# Supply.net
KiCad netlist of a schematic drawn in Altium Designer
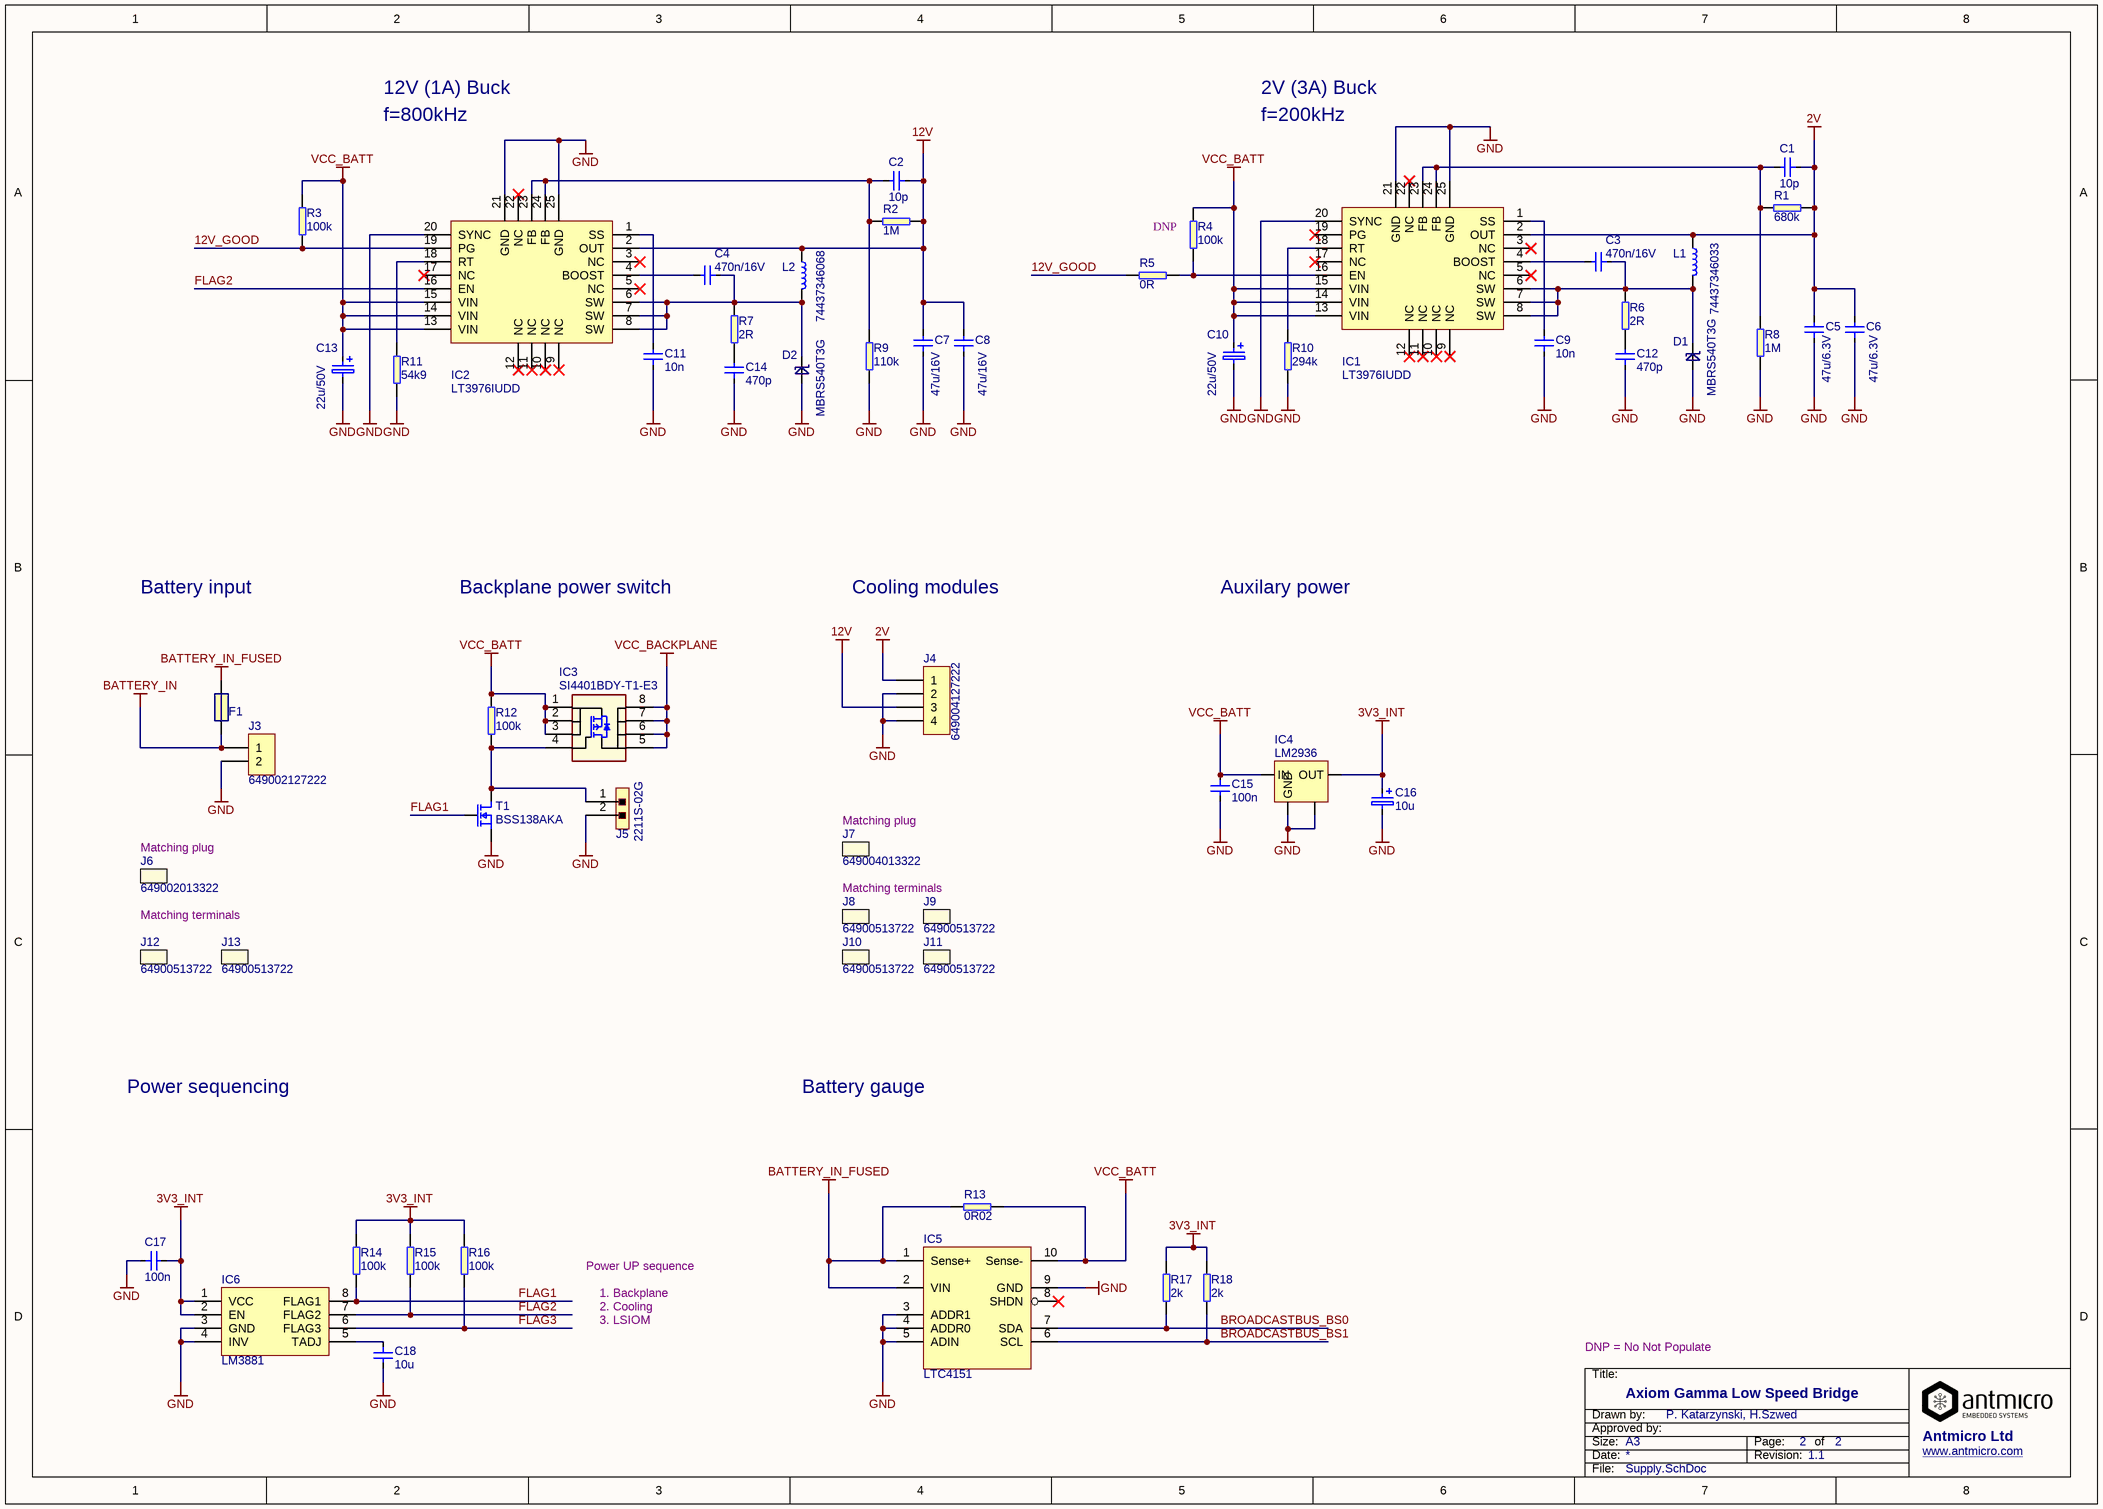
[diagram p0: Supply.SchDoc]

(export (version "E")
  (design (tool "Eeschema 10.0.6"))
  (components
    (comp (ref "C1")
      (value "10p")
      (footprint "0402")
      (description "MLCC SMT Capacitor 0402")
      (fields (field (name "PART NUMBER") "C_10n_0402") (field (name "MANUFACTURER") "AVX"))
      (libsource (lib "Axiom_Gamma_LSB") (part "C_0402"))
    )
    (comp (ref "C2")
      (value "10p")
      (footprint "0402")
      (description "MLCC SMT Capacitor 0402")
      (fields (field (name "PART NUMBER") "C_10n_0402") (field (name "MANUFACTURER") "AVX"))
      (libsource (lib "Axiom_Gamma_LSB") (part "C_0402"))
    )
    (comp (ref "C3")
      (value "470n/16V")
      (footprint "0402")
      (description "MLCC SMT Capacitor 0402")
      (fields (field (name "PART NUMBER") "C_10n_0402") (field (name "MANUFACTURER") "AVX"))
      (libsource (lib "Axiom_Gamma_LSB") (part "C_0402"))
    )
    (comp (ref "C4")
      (value "470n/16V")
      (footprint "0402")
      (description "MLCC SMT Capacitor 0402")
      (fields (field (name "PART NUMBER") "C_10n_0402") (field (name "MANUFACTURER") "AVX"))
      (libsource (lib "Axiom_Gamma_LSB") (part "C_0402"))
    )
    (comp (ref "C5")
      (value "47u/6.3V")
      (footprint "1206")
      (description "MLCC SMT Capacitor 1206")
      (fields (field (name "PART NUMBER") "C_47u_1206") (field (name "MANUFACTURER") "MURATA"))
      (libsource (lib "Axiom_Gamma_LSB") (part "C_1206"))
    )
    (comp (ref "C6")
      (value "47u/6.3V")
      (footprint "1206")
      (description "MLCC SMT Capacitor 1206")
      (fields (field (name "PART NUMBER") "C_47u_1206") (field (name "MANUFACTURER") "MURATA"))
      (libsource (lib "Axiom_Gamma_LSB") (part "C_1206"))
    )
    (comp (ref "C7")
      (value "47u/16V")
      (footprint "1206")
      (description "MLCC SMT Capacitor 1206")
      (fields (field (name "PART NUMBER") "C_47u_1206") (field (name "MANUFACTURER") "MURATA"))
      (libsource (lib "Axiom_Gamma_LSB") (part "C_1206"))
    )
    (comp (ref "C8")
      (value "47u/16V")
      (footprint "1206")
      (description "MLCC SMT Capacitor 1206")
      (fields (field (name "PART NUMBER") "C_47u_1206") (field (name "MANUFACTURER") "MURATA"))
      (libsource (lib "Axiom_Gamma_LSB") (part "C_1206"))
    )
    (comp (ref "C9")
      (value "10n")
      (footprint "0402")
      (description "MLCC SMT Capacitor 0402")
      (fields (field (name "PART NUMBER") "C_10n_0402") (field (name "MANUFACTURER") "AVX"))
      (libsource (lib "Axiom_Gamma_LSB") (part "C_0402"))
    )
    (comp (ref "C10")
      (value "22u/50V")
      (footprint "KEMET_X")
      (description "Tantalum SMT Capacitor Case KEMET_X")
      (fields (field (name "PART NUMBER") "C_22u_KEMET_X") (field (name "MANUFACTURER") "KEMET"))
      (libsource (lib "Axiom_Gamma_LSB") (part "CPol_X"))
    )
    (comp (ref "C11")
      (value "10n")
      (footprint "0402")
      (description "MLCC SMT Capacitor 0402")
      (fields (field (name "PART NUMBER") "C_10n_0402") (field (name "MANUFACTURER") "AVX"))
      (libsource (lib "Axiom_Gamma_LSB") (part "C_0402"))
    )
    (comp (ref "C12")
      (value "470p")
      (footprint "0402")
      (description "MLCC SMT Capacitor 0402")
      (fields (field (name "PART NUMBER") "C_10n_0402") (field (name "MANUFACTURER") "AVX"))
      (libsource (lib "Axiom_Gamma_LSB") (part "C_0402"))
    )
    (comp (ref "C13")
      (value "22u/50V")
      (footprint "KEMET_X")
      (description "Tantalum SMT Capacitor Case KEMET_X")
      (fields (field (name "PART NUMBER") "C_22u_KEMET_X") (field (name "MANUFACTURER") "KEMET"))
      (libsource (lib "Axiom_Gamma_LSB") (part "CPol_X"))
    )
    (comp (ref "C14")
      (value "470p")
      (footprint "0402")
      (description "MLCC SMT Capacitor 0402")
      (fields (field (name "PART NUMBER") "C_10n_0402") (field (name "MANUFACTURER") "AVX"))
      (libsource (lib "Axiom_Gamma_LSB") (part "C_0402"))
    )
    (comp (ref "C15")
      (value "100n")
      (footprint "0603")
      (description "MLCC SMT Capacitor  0603")
      (fields (field (name "PART NUMBER") "C_10u_0603") (field (name "MANUFACTURER") "MULTICOMP"))
      (libsource (lib "Axiom_Gamma_LSB") (part "C_0603"))
    )
    (comp (ref "C16")
      (value "10u")
      (footprint "KEMET_A")
      (description "Tantalum SMT Capacitor Case KEMET_A")
      (fields (field (name "PART NUMBER") "C_10u_KEMET_A") (field (name "MANUFACTURER") "VISHAY"))
      (libsource (lib "Axiom_Gamma_LSB") (part "CPol_A"))
    )
    (comp (ref "C17")
      (value "100n")
      (footprint "0603")
      (description "MLCC SMT Capacitor  0603")
      (fields (field (name "PART NUMBER") "C_10u_0603") (field (name "MANUFACTURER") "MULTICOMP"))
      (libsource (lib "Axiom_Gamma_LSB") (part "C_0603"))
    )
    (comp (ref "C18")
      (value "10u")
      (footprint "0603")
      (description "MLCC SMT Capacitor  0603")
      (fields (field (name "PART NUMBER") "C_10u_0603") (field (name "MANUFACTURER") "MULTICOMP"))
      (libsource (lib "Axiom_Gamma_LSB") (part "C_0603"))
    )
    (comp (ref "D1")
      (value "MBRS540T3G")
      (footprint "SMC-403-03")
      (description "ON SEMICONDUCTOR  MBRS540T3G  Rectifier Diode, Single, 40 V, 5 A, 500 mV, 190 A, 150 °C")
      (fields (field (name "MANUFACTURER") "ON SEMICONDUCTOR"))
      (libsource (lib "Axiom_Gamma_LSB") (part "Diode Schottky"))
    )
    (comp (ref "D2")
      (value "MBRS540T3G")
      (footprint "SMC-403-03")
      (description "ON SEMICONDUCTOR  MBRS540T3G  Rectifier Diode, Single, 40 V, 5 A, 500 mV, 190 A, 150 °C")
      (fields (field (name "MANUFACTURER") "ON SEMICONDUCTOR"))
      (libsource (lib "Axiom_Gamma_LSB") (part "Diode Schottky"))
    )
    (comp (ref "F1")
      (value "MC12CF")
      (footprint "1206")
      (fields (field (name "MANUFACTURER") "MULTICOMP"))
      (libsource (lib "Axiom_Gamma_LSB") (part "Fuse"))
    )
    (comp (ref "IC1")
      (value "LT3976IUDD")
      (footprint "QFN-24_3x5mm")
      (fields (field (name "MANUFACTURER") "LINEAR TECHNOLOGY"))
      (libsource (lib "Axiom_Gamma_LSB") (part "LT3976IUDD"))
    )
    (comp (ref "IC2")
      (value "LT3976IUDD")
      (footprint "QFN-24_3x5mm")
      (fields (field (name "MANUFACTURER") "LINEAR TECHNOLOGY"))
      (libsource (lib "Axiom_Gamma_LSB") (part "LT3976IUDD"))
    )
    (comp (ref "IC3")
      (value "SI4401BDY-T1-E3")
      (footprint "SOIC-SN8_M")
      (description "VISHAY  SI4401BDY-T1-E3  MOSFET Transistor, P Channel, -8.7 A, -40 V, 0.011 ohm, -10 V, -3 V")
      (fields (field (name "MANUFACTURER") "VISHAY"))
      (libsource (lib "Axiom_Gamma_LSB") (part "SI4447DY-T1-E3"))
    )
    (comp (ref "IC4")
      (value "LM2936")
      (footprint "SOT223")
      (fields (field (name "MANUFACTURER") "TEXAS INSTRUMENTS"))
      (libsource (lib "Axiom_Gamma_LSB") (part "LM2936"))
    )
    (comp (ref "IC5")
      (value "LTC4151")
      (footprint "MSOP10")
      (fields (field (name "MANUFACTURER") "LINEAR TECHNOLOGY"))
      (libsource (lib "Axiom_Gamma_LSB") (part "LTC4151"))
    )
    (comp (ref "IC6")
      (value "LM3881")
      (footprint "MSOP-8")
      (description "TEXAS INSTRUMENTS  LM3881MME/NOPB  Power Sequencer, 3-Monitors, 2.7V-5.5Vin,VSSOP-8")
      (fields (field (name "MANUFACTURER") "TEXAS INSTRUMENTS"))
      (libsource (lib "Axiom_Gamma_LSB") (part "LM3881"))
    )
    (comp (ref "J3")
      (value "649002127222")
      (footprint "WE_649002127222")
      (description "4.20mm Male Single Row Angled Header w. Mounting Pegs WR-MPC4")
      (fields (field (name "PART NUMBER") "WE_649002127222") (field (name "MANUFACTURER") "WURTH ELEKTRONIC"))
      (libsource (lib "Axiom_Gamma_LSB") (part "WE_649002127222"))
    )
    (comp (ref "J4")
      (value "649004127222")
      (footprint "WE_649004127222")
      (description "4.20mm Male Single Row Angled Header w. Mounting Pegs WR-MPC4")
      (fields (field (name "PART NUMBER") "WE_649004127222") (field (name "MANUFACTURER") "WURTH ELEKTRONIC"))
      (libsource (lib "Axiom_Gamma_LSB") (part "WE_649004127222"))
    )
    (comp (ref "J5")
      (value "2211S-02G")
      (footprint "HEADER_1X2_male 2.54mm Angle")
      (description "1x2 pinhead male angle")
      (fields
        (field (name "PART NUMBER") "HEADER_1X2_male_angle")
        (field (name "Comment") "1x2 pinhead 2.54mm male")
      )
      (libsource (lib "Axiom_Gamma_LSB") (part "HEADER_1X2_male_angle"))
    )
    (comp (ref "J6")
      (value "649002013322")
      (fields (field (name "MANUFACTURER") "Wuerth Elektronik"))
      (libsource (lib "Axiom_Gamma_LSB") (part "GENERIC_BOM_ONLY"))
    )
    (comp (ref "J7")
      (value "649004013322")
      (fields (field (name "MANUFACTURER") "Wuerth Elektronik"))
      (libsource (lib "Axiom_Gamma_LSB") (part "GENERIC_BOM_ONLY"))
    )
    (comp (ref "J8")
      (value "64900513722")
      (fields (field (name "MANUFACTURER") "Wuerth Elektronik"))
      (libsource (lib "Axiom_Gamma_LSB") (part "GENERIC_BOM_ONLY"))
    )
    (comp (ref "J9")
      (value "64900513722")
      (fields (field (name "MANUFACTURER") "Wuerth Elektronik"))
      (libsource (lib "Axiom_Gamma_LSB") (part "GENERIC_BOM_ONLY"))
    )
    (comp (ref "J10")
      (value "64900513722")
      (fields (field (name "MANUFACTURER") "Wuerth Elektronik"))
      (libsource (lib "Axiom_Gamma_LSB") (part "GENERIC_BOM_ONLY"))
    )
    (comp (ref "J11")
      (value "64900513722")
      (fields (field (name "MANUFACTURER") "Wuerth Elektronik"))
      (libsource (lib "Axiom_Gamma_LSB") (part "GENERIC_BOM_ONLY"))
    )
    (comp (ref "J12")
      (value "64900513722")
      (fields (field (name "MANUFACTURER") "Wuerth Elektronik"))
      (libsource (lib "Axiom_Gamma_LSB") (part "GENERIC_BOM_ONLY"))
    )
    (comp (ref "J13")
      (value "64900513722")
      (fields (field (name "MANUFACTURER") "Wuerth Elektronik"))
      (libsource (lib "Axiom_Gamma_LSB") (part "GENERIC_BOM_ONLY"))
    )
    (comp (ref "L1")
      (value "74437346033")
      (footprint "WE-LHMI")
      (description "3.3 uH, 5.0A, 0.03 ohm, SMD Power Inductor")
      (fields
        (field (name "PART NUMBER") "Wurth-74437346033")
        (field (name "MANUFACTURER") "WURTH ELEKTRONIK")
      )
      (libsource (lib "Axiom_Gamma_LSB") (part "Inductor SMT"))
    )
    (comp (ref "L2")
      (value "74437346068")
      (footprint "WE-LHMI")
      (description "6.8 uH, 3.4A, 0.054 ohm, SMD Power Inductor")
      (fields
        (field (name "PART NUMBER") "Wurth-74437346068")
        (field (name "MANUFACTURER") "WURTH ELEKTRONIK")
      )
      (libsource (lib "Axiom_Gamma_LSB") (part "Inductor SMT"))
    )
    (comp (ref "R1")
      (value "680k")
      (footprint "0402")
      (description "SMT Resistor 0402")
      (fields (field (name "PART NUMBER") "R_2R_0402") (field (name "MANUFACTURER") "MULTICOMP"))
      (libsource (lib "Axiom_Gamma_LSB") (part "R_0402"))
    )
    (comp (ref "R2")
      (value "1M")
      (footprint "0603")
      (description "SMT Resistor 0603")
      (fields (field (name "PART NUMBER") "R_1M_0603_0.1%") (field (name "MANUFACTURER") "TE"))
      (libsource (lib "") (part "R_0603_1"))
    )
    (comp (ref "R3")
      (value "100k")
      (footprint "0603")
      (description "SMT Resistor 0603")
      (fields (field (name "PART NUMBER") "R_1M_0603_0.1%") (field (name "MANUFACTURER") "TE"))
      (libsource (lib "Axiom_Gamma_LSB") (part "R_0603"))
    )
    (comp (ref "R4")
      (value "100k")
      (footprint "0603")
      (description "SMT Resistor 0603")
      (fields (field (name "PART NUMBER") "R_1M_0603_0.1%") (field (name "MANUFACTURER") "TE"))
      (libsource (lib "Axiom_Gamma_LSB") (part "R_0603"))
    )
    (comp (ref "R5")
      (value "0R")
      (footprint "0603")
      (description "SMT Resistor 0603")
      (fields (field (name "PART NUMBER") "R_1M_0603_0.1%") (field (name "MANUFACTURER") "TE"))
      (libsource (lib "") (part "R_0603_2"))
    )
    (comp (ref "R6")
      (value "2R")
      (footprint "0402")
      (description "SMT Resistor 0402")
      (fields (field (name "PART NUMBER") "R_2R_0402") (field (name "MANUFACTURER") "MULTICOMP"))
      (libsource (lib "Axiom_Gamma_LSB") (part "R_0402"))
    )
    (comp (ref "R7")
      (value "2R")
      (footprint "0402")
      (description "SMT Resistor 0402")
      (fields (field (name "PART NUMBER") "R_2R_0402") (field (name "MANUFACTURER") "MULTICOMP"))
      (libsource (lib "Axiom_Gamma_LSB") (part "R_0402"))
    )
    (comp (ref "R8")
      (value "1M")
      (footprint "0603")
      (description "SMT Resistor 0603")
      (fields (field (name "PART NUMBER") "R_1M_0603_0.1%") (field (name "MANUFACTURER") "TE"))
      (libsource (lib "") (part "R_0603_3"))
    )
    (comp (ref "R9")
      (value "110k")
      (footprint "0603")
      (description "SMT Resistor 0603")
      (fields (field (name "PART NUMBER") "R_1M_0603_0.1%") (field (name "MANUFACTURER") "TE"))
      (libsource (lib "") (part "R_0603_2"))
    )
    (comp (ref "R10")
      (value "294k")
      (footprint "0402")
      (description "SMT Resistor 0402")
      (fields (field (name "PART NUMBER") "R_2R_0402") (field (name "MANUFACTURER") "MULTICOMP"))
      (libsource (lib "") (part "R_0402_1"))
    )
    (comp (ref "R11")
      (value "54k9")
      (footprint "0402")
      (description "SMT Resistor 0402")
      (fields (field (name "PART NUMBER") "R_2R_0402") (field (name "MANUFACTURER") "MULTICOMP"))
      (libsource (lib "Axiom_Gamma_LSB") (part "R_0402"))
    )
    (comp (ref "R12")
      (value "100k")
      (footprint "0603")
      (description "SMT Resistor 0603")
      (fields (field (name "PART NUMBER") "R_1M_0603_0.1%") (field (name "MANUFACTURER") "TE"))
      (libsource (lib "Axiom_Gamma_LSB") (part "R_0603"))
    )
    (comp (ref "R13")
      (value "0R02")
      (footprint "2512")
      (description "SMT Resistor 2512")
      (fields (field (name "PART NUMBER") "R_0R02_2512") (field (name "MANUFACTURER") "BOURNS"))
      (libsource (lib "Axiom_Gamma_LSB") (part "R_2512"))
    )
    (comp (ref "R14")
      (value "100k")
      (footprint "0603")
      (description "SMT Resistor 0603")
      (fields (field (name "PART NUMBER") "R_1M_0603_0.1%") (field (name "MANUFACTURER") "TE"))
      (libsource (lib "Axiom_Gamma_LSB") (part "R_0603"))
    )
    (comp (ref "R15")
      (value "100k")
      (footprint "0603")
      (description "SMT Resistor 0603")
      (fields (field (name "PART NUMBER") "R_1M_0603_0.1%") (field (name "MANUFACTURER") "TE"))
      (libsource (lib "Axiom_Gamma_LSB") (part "R_0603"))
    )
    (comp (ref "R16")
      (value "100k")
      (footprint "0603")
      (description "SMT Resistor 0603")
      (fields (field (name "PART NUMBER") "R_1M_0603_0.1%") (field (name "MANUFACTURER") "TE"))
      (libsource (lib "Axiom_Gamma_LSB") (part "R_0603"))
    )
    (comp (ref "R17")
      (value "2k")
      (footprint "0603")
      (description "SMT Resistor 0603")
      (fields (field (name "PART NUMBER") "R_1M_0603_0.1%") (field (name "MANUFACTURER") "TE"))
      (libsource (lib "Axiom_Gamma_LSB") (part "R_0603"))
    )
    (comp (ref "R18")
      (value "2k")
      (footprint "0603")
      (description "SMT Resistor 0603")
      (fields (field (name "PART NUMBER") "R_1M_0603_0.1%") (field (name "MANUFACTURER") "TE"))
      (libsource (lib "Axiom_Gamma_LSB") (part "R_0603"))
    )
    (comp (ref "T1")
      (value "BSS138AKA")
      (footprint "SOT-23")
      (description "MOSFET, N CH, 60V, 0.2A")
      (fields (field (name "PART NUMBER") "BSS138") (field (name "MANUFACTURER") "NXP"))
      (libsource (lib "Axiom_Gamma_LSB") (part "NMOS"))
    )
  )
  (nets
    (net (code "1") (name "/12V_GOOD") (class "Default")
      (node (ref "IC2") (pin "19") (pinfunction "PG_19") (pintype "passive"))
      (node (ref "R3") (pin "1") (pintype "passive"))
      (node (ref "R5") (pin "1") (pintype "passive"))
    )
    (net (code "2") (name "/BROADCASTBUS_BS0") (class "Default")
      (node (ref "IC5") (pin "7") (pinfunction "SDA_7") (pintype "passive"))
      (node (ref "R17") (pin "1") (pintype "passive"))
    )
    (net (code "3") (name "/BROADCASTBUS_BS1") (class "Default")
      (node (ref "IC5") (pin "6") (pinfunction "SCL_6") (pintype "passive"))
      (node (ref "R18") (pin "1") (pintype "passive"))
    )
    (net (code "4") (name "/FLAG1") (class "Default")
      (node (ref "IC6") (pin "8") (pinfunction "FLAG1_8") (pintype "passive"))
      (node (ref "R14") (pin "1") (pintype "passive"))
      (node (ref "T1") (pin "1") (pinfunction "G_1") (pintype "passive"))
    )
    (net (code "5") (name "/FLAG2") (class "Default")
      (node (ref "IC2") (pin "16") (pinfunction "EN_16") (pintype "passive"))
      (node (ref "IC6") (pin "7") (pinfunction "FLAG2_7") (pintype "passive"))
      (node (ref "R15") (pin "1") (pintype "passive"))
    )
    (net (code "6") (name "/FLAG3") (class "Default")
      (node (ref "IC6") (pin "6") (pinfunction "FLAG3_6") (pintype "passive"))
      (node (ref "R16") (pin "1") (pintype "passive"))
    )
    (net (code "7") (name "2V") (class "Default")
      (node (ref "C1") (pin "1") (pinfunction "1_1") (pintype "passive"))
      (node (ref "C5") (pin "2") (pinfunction "2_2") (pintype "passive"))
      (node (ref "C6") (pin "2") (pinfunction "2_2") (pintype "passive"))
      (node (ref "IC1") (pin "2") (pinfunction "OUT_2") (pintype "passive"))
      (node (ref "J4") (pin "1") (pinfunction "1_1") (pintype "passive"))
      (node (ref "L1") (pin "2") (pintype "passive"))
      (node (ref "R1") (pin "2") (pintype "passive"))
    )
    (net (code "8") (name "3V3_INT") (class "Default")
      (node (ref "C16") (pin "1") (pinfunction "1_1") (pintype "passive"))
      (node (ref "C17") (pin "2") (pinfunction "2_2") (pintype "passive"))
      (node (ref "IC4") (pin "3") (pinfunction "OUT_3") (pintype "passive"))
      (node (ref "IC6") (pin "1") (pinfunction "VCC_1") (pintype "passive"))
      (node (ref "IC6") (pin "2") (pinfunction "EN_2") (pintype "power_in"))
      (node (ref "R14") (pin "2") (pintype "passive"))
      (node (ref "R15") (pin "2") (pintype "passive"))
      (node (ref "R16") (pin "2") (pintype "passive"))
      (node (ref "R17") (pin "2") (pintype "passive"))
      (node (ref "R18") (pin "2") (pintype "passive"))
    )
    (net (code "9") (name "12V") (class "Default")
      (node (ref "C2") (pin "1") (pinfunction "1_1") (pintype "passive"))
      (node (ref "C7") (pin "2") (pinfunction "2_2") (pintype "passive"))
      (node (ref "C8") (pin "2") (pinfunction "2_2") (pintype "passive"))
      (node (ref "IC2") (pin "2") (pinfunction "OUT_2") (pintype "passive"))
      (node (ref "J4") (pin "3") (pinfunction "3_3") (pintype "passive"))
      (node (ref "L2") (pin "2") (pintype "passive"))
      (node (ref "R2") (pin "1") (pintype "passive"))
    )
    (net (code "10") (name "BATTERY_IN") (class "Default")
      (node (ref "F1") (pin "1") (pinfunction "1_1") (pintype "passive"))
      (node (ref "J3") (pin "1") (pinfunction "1_1") (pintype "passive"))
    )
    (net (code "11") (name "BATTERY_IN_FUSED") (class "Default")
      (node (ref "F1") (pin "2") (pinfunction "2_2") (pintype "passive"))
      (node (ref "IC5") (pin "1") (pinfunction "Sense+_1") (pintype "passive"))
      (node (ref "IC5") (pin "2") (pinfunction "VIN_2") (pintype "passive"))
      (node (ref "R13") (pin "1") (pintype "passive"))
    )
    (net (code "12") (name "GND") (class "Default")
      (node (ref "C10") (pin "2") (pinfunction "2_2") (pintype "passive"))
      (node (ref "C11") (pin "1") (pinfunction "1_1") (pintype "passive"))
      (node (ref "C12") (pin "1") (pinfunction "1_1") (pintype "passive"))
      (node (ref "C13") (pin "2") (pinfunction "2_2") (pintype "passive"))
      (node (ref "C14") (pin "1") (pinfunction "1_1") (pintype "passive"))
      (node (ref "C15") (pin "2") (pinfunction "2_2") (pintype "passive"))
      (node (ref "C16") (pin "2") (pinfunction "2_2") (pintype "passive"))
      (node (ref "C17") (pin "1") (pinfunction "1_1") (pintype "passive"))
      (node (ref "C18") (pin "2") (pinfunction "2_2") (pintype "passive"))
      (node (ref "C5") (pin "1") (pinfunction "1_1") (pintype "passive"))
      (node (ref "C6") (pin "1") (pinfunction "1_1") (pintype "passive"))
      (node (ref "C7") (pin "1") (pinfunction "1_1") (pintype "passive"))
      (node (ref "C8") (pin "1") (pinfunction "1_1") (pintype "passive"))
      (node (ref "C9") (pin "1") (pinfunction "1_1") (pintype "passive"))
      (node (ref "D1") (pin "A") (pinfunction "A_A") (pintype "passive"))
      (node (ref "D2") (pin "A") (pinfunction "A_A") (pintype "passive"))
      (node (ref "IC1") (pin "20") (pinfunction "SYNC_20") (pintype "passive"))
      (node (ref "IC1") (pin "21") (pinfunction "GND_21") (pintype "passive"))
      (node (ref "IC1") (pin "25") (pinfunction "GND_25") (pintype "passive"))
      (node (ref "IC2") (pin "20") (pinfunction "SYNC_20") (pintype "passive"))
      (node (ref "IC2") (pin "21") (pinfunction "GND_21") (pintype "passive"))
      (node (ref "IC2") (pin "25") (pinfunction "GND_25") (pintype "passive"))
      (node (ref "IC4") (pin "2") (pinfunction "GND_2") (pintype "power_in"))
      (node (ref "IC4") (pin "4") (pinfunction "GND_4") (pintype "passive"))
      (node (ref "IC5") (pin "3") (pinfunction "ADDR1_3") (pintype "passive"))
      (node (ref "IC5") (pin "4") (pinfunction "ADDR0_4") (pintype "passive"))
      (node (ref "IC5") (pin "5") (pinfunction "ADIN_5") (pintype "passive"))
      (node (ref "IC5") (pin "9") (pinfunction "GND_9") (pintype "passive"))
      (node (ref "IC6") (pin "3") (pinfunction "GND_3") (pintype "power_in"))
      (node (ref "IC6") (pin "4") (pinfunction "INV_4") (pintype "passive"))
      (node (ref "J3") (pin "2") (pinfunction "2_2") (pintype "passive"))
      (node (ref "J4") (pin "2") (pinfunction "2_2") (pintype "passive"))
      (node (ref "J4") (pin "4") (pinfunction "4_4") (pintype "passive"))
      (node (ref "J5") (pin "2") (pinfunction "2_2") (pintype "passive"))
      (node (ref "R10") (pin "1") (pintype "passive"))
      (node (ref "R11") (pin "1") (pintype "passive"))
      (node (ref "R8") (pin "2") (pintype "passive"))
      (node (ref "R9") (pin "1") (pintype "passive"))
      (node (ref "T1") (pin "2") (pinfunction "S_2") (pintype "passive"))
    )
    (net (code "13") (name "Net-(C1-Pad2)") (class "Default")
      (node (ref "C1") (pin "2") (pinfunction "2_2") (pintype "passive"))
      (node (ref "IC1") (pin "23") (pinfunction "FB_23") (pintype "passive"))
      (node (ref "IC1") (pin "24") (pinfunction "FB_24") (pintype "passive"))
      (node (ref "R1") (pin "1") (pintype "passive"))
      (node (ref "R8") (pin "1") (pintype "passive"))
    )
    (net (code "14") (name "Net-(C2-Pad2)") (class "Default")
      (node (ref "C2") (pin "2") (pinfunction "2_2") (pintype "passive"))
      (node (ref "IC2") (pin "23") (pinfunction "FB_23") (pintype "passive"))
      (node (ref "IC2") (pin "24") (pinfunction "FB_24") (pintype "passive"))
      (node (ref "R2") (pin "2") (pintype "passive"))
      (node (ref "R9") (pin "2") (pintype "passive"))
    )
    (net (code "15") (name "Net-(C3-Pad1)") (class "Default")
      (node (ref "C3") (pin "1") (pinfunction "1_1") (pintype "passive"))
      (node (ref "D1") (pin "C") (pinfunction "C_C") (pintype "passive"))
      (node (ref "IC1") (pin "6") (pinfunction "SW_6") (pintype "passive"))
      (node (ref "IC1") (pin "7") (pinfunction "SW_7") (pintype "passive"))
      (node (ref "IC1") (pin "8") (pinfunction "SW_8") (pintype "passive"))
      (node (ref "L1") (pin "1") (pintype "passive"))
      (node (ref "R6") (pin "2") (pintype "passive"))
    )
    (net (code "16") (name "Net-(C4-Pad1)") (class "Default")
      (node (ref "C4") (pin "1") (pinfunction "1_1") (pintype "passive"))
      (node (ref "D2") (pin "C") (pinfunction "C_C") (pintype "passive"))
      (node (ref "IC2") (pin "6") (pinfunction "SW_6") (pintype "passive"))
      (node (ref "IC2") (pin "7") (pinfunction "SW_7") (pintype "passive"))
      (node (ref "IC2") (pin "8") (pinfunction "SW_8") (pintype "passive"))
      (node (ref "L2") (pin "1") (pintype "passive"))
      (node (ref "R7") (pin "2") (pintype "passive"))
    )
    (net (code "17") (name "Net-(C12-Pad2)") (class "Default")
      (node (ref "C12") (pin "2") (pinfunction "2_2") (pintype "passive"))
      (node (ref "R6") (pin "1") (pintype "passive"))
    )
    (net (code "18") (name "Net-(C14-Pad2)") (class "Default")
      (node (ref "C14") (pin "2") (pinfunction "2_2") (pintype "passive"))
      (node (ref "R7") (pin "1") (pintype "passive"))
    )
    (net (code "19") (name "Net-(IC1-BOOST)") (class "Default")
      (node (ref "C3") (pin "2") (pinfunction "2_2") (pintype "passive"))
      (node (ref "IC1") (pin "4") (pinfunction "BOOST_4") (pintype "passive"))
    )
    (net (code "20") (name "Net-(IC1-EN)") (class "Default")
      (node (ref "IC1") (pin "16") (pinfunction "EN_16") (pintype "passive"))
      (node (ref "R4") (pin "1") (pintype "passive"))
      (node (ref "R5") (pin "2") (pintype "passive"))
    )
    (net (code "21") (name "Net-(IC1-RT)") (class "Default")
      (node (ref "IC1") (pin "18") (pinfunction "RT_18") (pintype "passive"))
      (node (ref "R10") (pin "2") (pintype "passive"))
    )
    (net (code "22") (name "Net-(IC1-SS)") (class "Default")
      (node (ref "C9") (pin "2") (pinfunction "2_2") (pintype "passive"))
      (node (ref "IC1") (pin "1") (pinfunction "SS_1") (pintype "passive"))
    )
    (net (code "23") (name "Net-(IC2-BOOST)") (class "Default")
      (node (ref "C4") (pin "2") (pinfunction "2_2") (pintype "passive"))
      (node (ref "IC2") (pin "4") (pinfunction "BOOST_4") (pintype "passive"))
    )
    (net (code "24") (name "Net-(IC2-RT)") (class "Default")
      (node (ref "IC2") (pin "18") (pinfunction "RT_18") (pintype "passive"))
      (node (ref "R11") (pin "2") (pintype "passive"))
    )
    (net (code "25") (name "Net-(IC2-SS)") (class "Default")
      (node (ref "C11") (pin "2") (pinfunction "2_2") (pintype "passive"))
      (node (ref "IC2") (pin "1") (pinfunction "SS_1") (pintype "passive"))
    )
    (net (code "26") (name "Net-(IC6-TADJ)") (class "Default")
      (node (ref "C18") (pin "1") (pinfunction "1_1") (pintype "passive"))
      (node (ref "IC6") (pin "5") (pinfunction "TADJ_5") (pintype "power_in"))
    )
    (net (code "27") (name "Net-(T1-D)") (class "Default")
      (node (ref "IC3") (pin "4") (pinfunction "4_4") (pintype "passive"))
      (node (ref "J5") (pin "1") (pinfunction "1_1") (pintype "passive"))
      (node (ref "R12") (pin "1") (pintype "passive"))
      (node (ref "T1") (pin "3") (pinfunction "D_3") (pintype "passive"))
    )
    (net (code "28") (name "VCC_BACKPLANE") (class "Default")
      (node (ref "IC3") (pin "5") (pinfunction "5_5") (pintype "passive"))
      (node (ref "IC3") (pin "6") (pinfunction "6_6") (pintype "passive"))
      (node (ref "IC3") (pin "7") (pinfunction "7_7") (pintype "passive"))
      (node (ref "IC3") (pin "8") (pinfunction "8_8") (pintype "passive"))
    )
    (net (code "29") (name "VCC_BATT") (class "Default")
      (node (ref "C10") (pin "1") (pinfunction "1_1") (pintype "passive"))
      (node (ref "C13") (pin "1") (pinfunction "1_1") (pintype "passive"))
      (node (ref "C15") (pin "1") (pinfunction "1_1") (pintype "passive"))
      (node (ref "IC1") (pin "13") (pinfunction "VIN_13") (pintype "passive"))
      (node (ref "IC1") (pin "14") (pinfunction "VIN_14") (pintype "passive"))
      (node (ref "IC1") (pin "15") (pinfunction "VIN_15") (pintype "passive"))
      (node (ref "IC2") (pin "13") (pinfunction "VIN_13") (pintype "passive"))
      (node (ref "IC2") (pin "14") (pinfunction "VIN_14") (pintype "passive"))
      (node (ref "IC2") (pin "15") (pinfunction "VIN_15") (pintype "passive"))
      (node (ref "IC3") (pin "1") (pinfunction "1_1") (pintype "passive"))
      (node (ref "IC3") (pin "2") (pinfunction "2_2") (pintype "passive"))
      (node (ref "IC3") (pin "3") (pinfunction "3_3") (pintype "passive"))
      (node (ref "IC4") (pin "1") (pinfunction "IN_1") (pintype "power_in"))
      (node (ref "IC5") (pin "10") (pinfunction "Sense-_10") (pintype "passive"))
      (node (ref "R12") (pin "2") (pintype "passive"))
      (node (ref "R13") (pin "2") (pintype "passive"))
      (node (ref "R3") (pin "2") (pintype "passive"))
      (node (ref "R4") (pin "2") (pintype "passive"))
    )
    (net (code "30") (name "unconnected-(IC1-NC-Pad3)") (class "Default")
      (node (ref "IC1") (pin "3") (pinfunction "NC_3") (pintype "passive+no_connect"))
    )
    (net (code "31") (name "unconnected-(IC1-NC-Pad5)") (class "Default")
      (node (ref "IC1") (pin "5") (pinfunction "NC_5") (pintype "passive+no_connect"))
    )
    (net (code "32") (name "unconnected-(IC1-NC-Pad9)") (class "Default")
      (node (ref "IC1") (pin "9") (pinfunction "NC_9") (pintype "passive+no_connect"))
    )
    (net (code "33") (name "unconnected-(IC1-NC-Pad10)") (class "Default")
      (node (ref "IC1") (pin "10") (pinfunction "NC_10") (pintype "passive+no_connect"))
    )
    (net (code "34") (name "unconnected-(IC1-NC-Pad11)") (class "Default")
      (node (ref "IC1") (pin "11") (pinfunction "NC_11") (pintype "passive+no_connect"))
    )
    (net (code "35") (name "unconnected-(IC1-NC-Pad12)") (class "Default")
      (node (ref "IC1") (pin "12") (pinfunction "NC_12") (pintype "passive+no_connect"))
    )
    (net (code "36") (name "unconnected-(IC1-NC-Pad17)") (class "Default")
      (node (ref "IC1") (pin "17") (pinfunction "NC_17") (pintype "passive+no_connect"))
    )
    (net (code "37") (name "unconnected-(IC1-NC-Pad22)") (class "Default")
      (node (ref "IC1") (pin "22") (pinfunction "NC_22") (pintype "passive+no_connect"))
    )
    (net (code "38") (name "unconnected-(IC1-PG-Pad19)") (class "Default")
      (node (ref "IC1") (pin "19") (pinfunction "PG_19") (pintype "passive+no_connect"))
    )
    (net (code "39") (name "unconnected-(IC2-NC-Pad3)") (class "Default")
      (node (ref "IC2") (pin "3") (pinfunction "NC_3") (pintype "passive+no_connect"))
    )
    (net (code "40") (name "unconnected-(IC2-NC-Pad5)") (class "Default")
      (node (ref "IC2") (pin "5") (pinfunction "NC_5") (pintype "passive+no_connect"))
    )
    (net (code "41") (name "unconnected-(IC2-NC-Pad9)") (class "Default")
      (node (ref "IC2") (pin "9") (pinfunction "NC_9") (pintype "passive+no_connect"))
    )
    (net (code "42") (name "unconnected-(IC2-NC-Pad10)") (class "Default")
      (node (ref "IC2") (pin "10") (pinfunction "NC_10") (pintype "passive+no_connect"))
    )
    (net (code "43") (name "unconnected-(IC2-NC-Pad11)") (class "Default")
      (node (ref "IC2") (pin "11") (pinfunction "NC_11") (pintype "passive+no_connect"))
    )
    (net (code "44") (name "unconnected-(IC2-NC-Pad12)") (class "Default")
      (node (ref "IC2") (pin "12") (pinfunction "NC_12") (pintype "passive+no_connect"))
    )
    (net (code "45") (name "unconnected-(IC2-NC-Pad17)") (class "Default")
      (node (ref "IC2") (pin "17") (pinfunction "NC_17") (pintype "passive+no_connect"))
    )
    (net (code "46") (name "unconnected-(IC2-NC-Pad22)") (class "Default")
      (node (ref "IC2") (pin "22") (pinfunction "NC_22") (pintype "passive+no_connect"))
    )
    (net (code "47") (name "unconnected-(IC5-SHDN-Pad8)") (class "Default")
      (node (ref "IC5") (pin "8") (pinfunction "SHDN_8") (pintype "passive+no_connect"))
    )
  )
)
